# E-18_M_2.net
KiCad netlist of a schematic drawn in Altium Designer
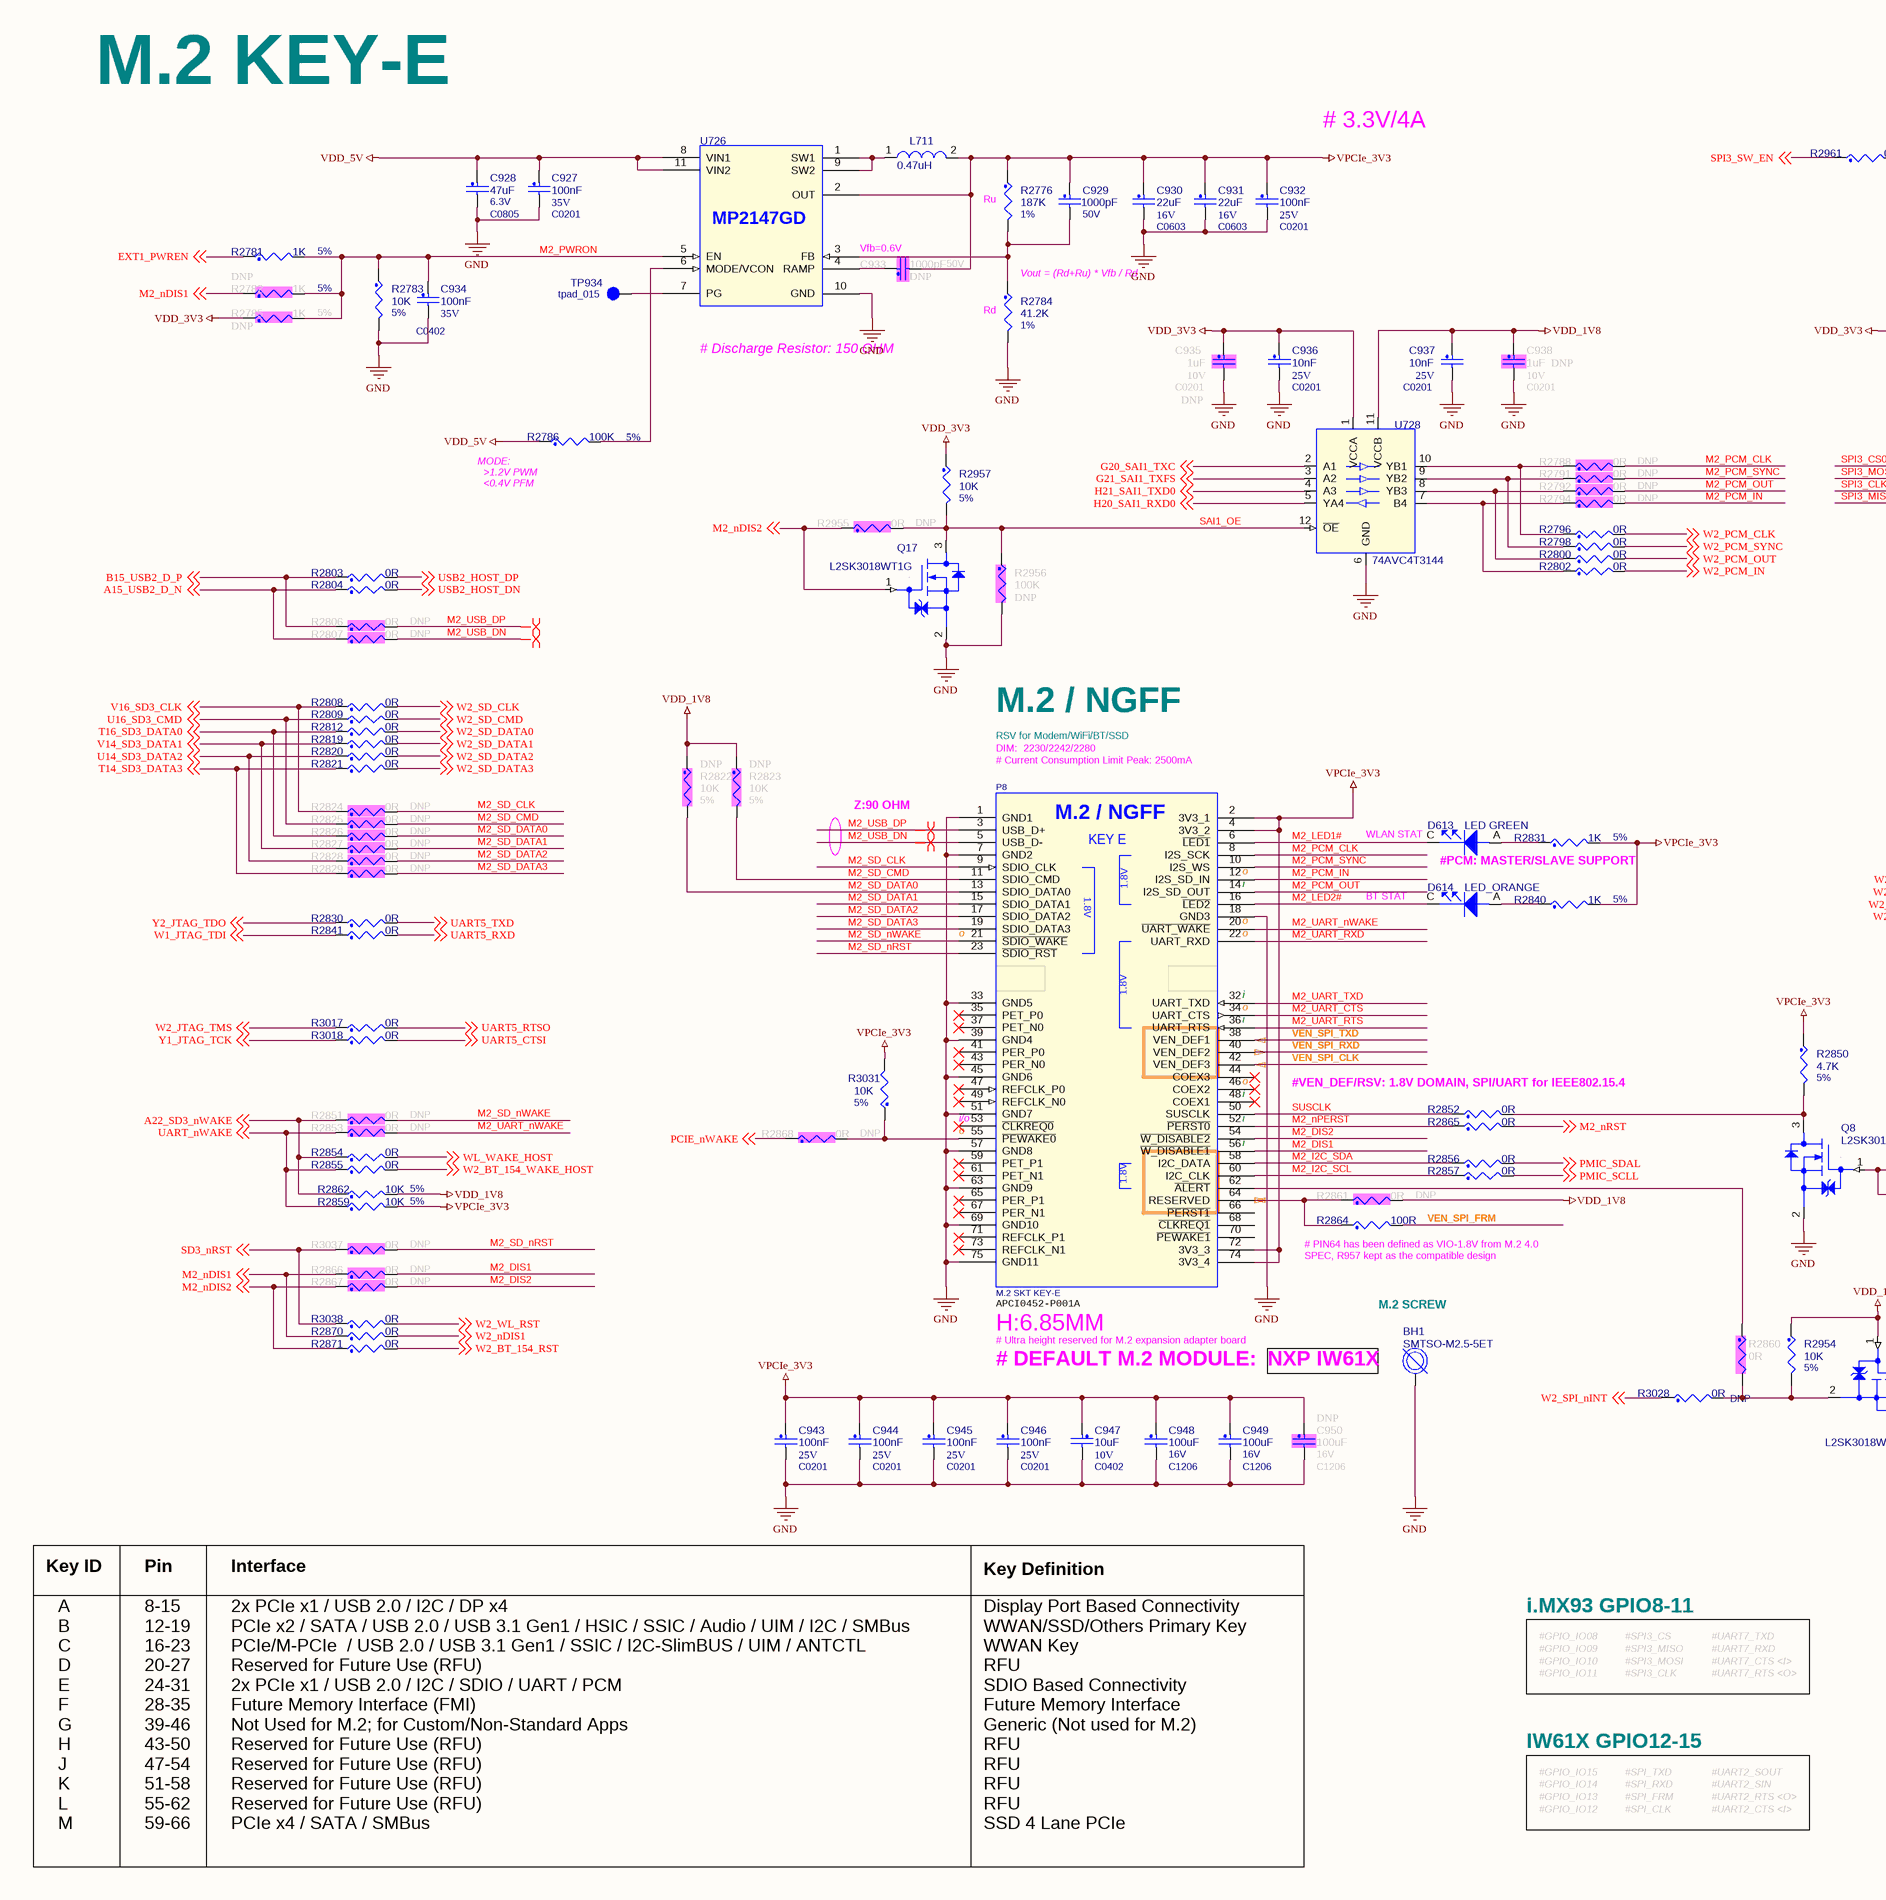
[diagram p0: E-18 M.2.SchDoc, left]
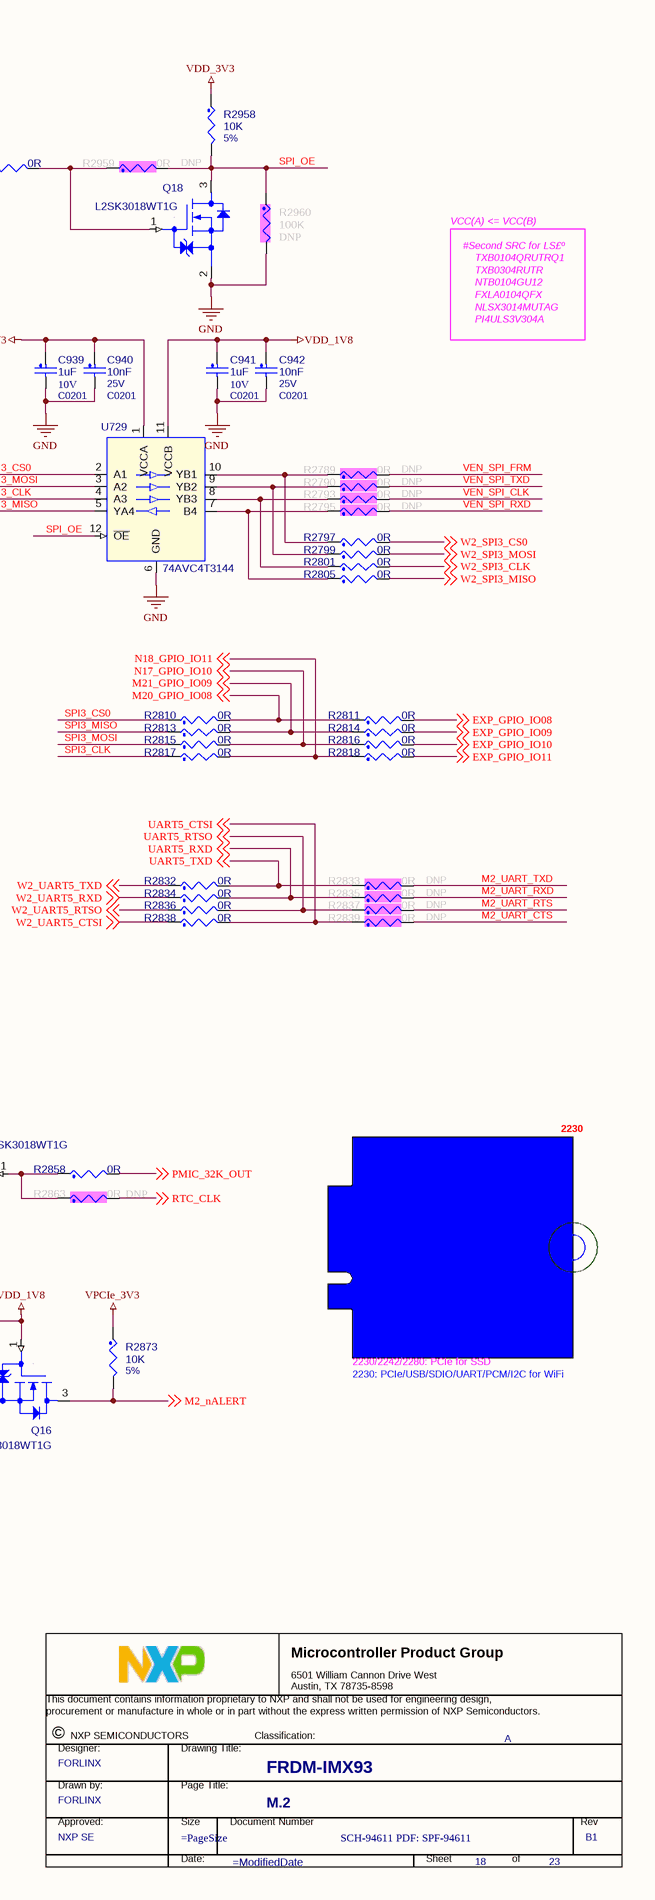
[diagram p1: E-18 M.2.SchDoc, right]

(export (version "E")
  (design (tool "Eeschema 10.0.6"))
  (components
    (comp (ref "BH1")
      (value "SMTSO-M2.5-5ET")
      (footprint "mh244-166t_202h")
      (description "M2mm,long 4mm")
      (libsource (lib "*") (part "MOUNT_HOLE"))
    )
    (comp (ref "C927")
      (value "100nF")
      (footprint "C0201")
      (description "0201,100nF,25V,+/-10%,X5R")
      (fields
        (field (name "VOLTAGE") "35V")
        (field (name "TOLERANCE") "10%")
        (field (name "PCB FOOTPRINT") "C0201")
      )
      (libsource (lib "*") (part "CAP_NP"))
    )
    (comp (ref "C928")
      (value "47uF")
      (footprint "C0805")
      (description "0805,47uF,10V,+/-20%,X5R")
      (fields
        (field (name "VOLTAGE") "6.3V")
        (field (name "TOLERANCE") "20%")
        (field (name "PCB FOOTPRINT") "C0805")
      )
      (libsource (lib "*") (part "CAP_NP"))
    )
    (comp (ref "C929")
      (value "1000pF")
      (footprint "C0402")
      (description "0402,1nF,50V,+/-10%,X7R")
      (fields (field (name "TOLERANCE") "5%") (field (name "VOLTAGE") "50V"))
      (libsource (lib "*") (part "CAP_NP"))
    )
    (comp (ref "C930")
      (value "22uF")
      (footprint "C0603")
      (description "0603,22uF,6.3V,+/-20%,X5R")
      (fields
        (field (name "TOLERANCE") "20%")
        (field (name "VOLTAGE") "16V")
        (field (name "PCB FOOTPRINT") "C0603")
      )
      (libsource (lib "*") (part "CAP_NP"))
    )
    (comp (ref "C931")
      (value "22uF")
      (footprint "C0603")
      (description "0603,22uF,6.3V,+/-20%,X5R")
      (fields
        (field (name "TOLERANCE") "20%")
        (field (name "VOLTAGE") "16V")
        (field (name "PCB FOOTPRINT") "C0603")
      )
      (libsource (lib "*") (part "CAP_NP"))
    )
    (comp (ref "C932")
      (value "100nF")
      (footprint "C0201")
      (description "0201,100nF,25V,+/-10%,X5R")
      (fields
        (field (name "VOLTAGE") "25V")
        (field (name "TOLERANCE") "10%")
        (field (name "PCB FOOTPRINT") "C0201")
      )
      (libsource (lib "*") (part "CAP_NP"))
    )
    (comp (ref "C933")
      (value "1000pF")
      (footprint "C0402")
      (description "0402,1nF,50V,+/-10%,X7R")
      (fields (field (name "ASSY_OPT") "DNP") (field (name "VOLTAGE") "50V") (field (name "TOLERANCE") "5%"))
      (libsource (lib "*") (part "CAP_NP"))
    )
    (comp (ref "C934")
      (value "100nF")
      (footprint "C0402")
      (description "0402,100nF,50V,+/-10%,X5R")
      (fields
        (field (name "TOLERANCE") "10%")
        (field (name "VOLTAGE") "35V")
        (field (name "PCB FOOTPRINT") "C0402")
      )
      (libsource (lib "*") (part "CAP_NP"))
    )
    (comp (ref "C935")
      (value "1uF")
      (footprint "C0201")
      (description "0201,1uF,10V,+/-20%,X5R")
      (fields
        (field (name "ASSY_OPT") "DNP")
        (field (name "TOLERANCE") "10%")
        (field (name "VOLTAGE") "10V")
        (field (name "PCB FOOTPRINT") "C0201")
      )
      (libsource (lib "*") (part "CAP_NP"))
    )
    (comp (ref "C936")
      (value "10nF")
      (footprint "C0201")
      (description "0201,10nF,25V,+/-10%,X7R")
      (fields
        (field (name "TOLERANCE") "10%")
        (field (name "VOLTAGE") "25V")
        (field (name "PCB FOOTPRINT") "C0201")
      )
      (libsource (lib "*") (part "CAP_NP"))
    )
    (comp (ref "C937")
      (value "10nF")
      (footprint "C0201")
      (description "0201,10nF,25V,+/-10%,X7R")
      (fields
        (field (name "TOLERANCE") "10%")
        (field (name "VOLTAGE") "25V")
        (field (name "PCB FOOTPRINT") "C0201")
      )
      (libsource (lib "*") (part "CAP_NP"))
    )
    (comp (ref "C938")
      (value "1uF")
      (footprint "C0201")
      (description "0201,1uF,10V,+/-20%,X5R")
      (fields
        (field (name "ASSY_OPT") "DNP")
        (field (name "TOLERANCE") "10%")
        (field (name "VOLTAGE") "10V")
        (field (name "PCB FOOTPRINT") "C0201")
      )
      (libsource (lib "*") (part "CAP_NP"))
    )
    (comp (ref "C939")
      (value "1uF")
      (footprint "C0201")
      (description "0201,1uF,10V,+/-20%,X5R")
      (fields
        (field (name "TOLERANCE") "10%")
        (field (name "VOLTAGE") "10V")
        (field (name "PCB FOOTPRINT") "C0201")
      )
      (libsource (lib "*") (part "CAP_NP"))
    )
    (comp (ref "C940")
      (value "10nF")
      (footprint "C0201")
      (description "0201,10nF,25V,+/-10%,X7R")
      (fields
        (field (name "VOLTAGE") "25V")
        (field (name "TOLERANCE") "10%")
        (field (name "PCB FOOTPRINT") "C0201")
      )
      (libsource (lib "*") (part "CAP_NP"))
    )
    (comp (ref "C941")
      (value "1uF")
      (footprint "C0201")
      (description "0201,1uF,10V,+/-20%,X5R")
      (fields
        (field (name "TOLERANCE") "10%")
        (field (name "VOLTAGE") "10V")
        (field (name "PCB FOOTPRINT") "C0201")
      )
      (libsource (lib "*") (part "CAP_NP"))
    )
    (comp (ref "C942")
      (value "10nF")
      (footprint "C0201")
      (description "0201,10nF,25V,+/-10%,X7R")
      (fields
        (field (name "VOLTAGE") "25V")
        (field (name "TOLERANCE") "10%")
        (field (name "PCB FOOTPRINT") "C0201")
      )
      (libsource (lib "*") (part "CAP_NP"))
    )
    (comp (ref "C943")
      (value "100nF")
      (footprint "C0201")
      (description "0201,100nF,25V,+/-10%,X5R")
      (fields
        (field (name "VOLTAGE") "25V")
        (field (name "TOLERANCE") "10%")
        (field (name "PCB FOOTPRINT") "C0201")
      )
      (libsource (lib "*") (part "CAP_NP"))
    )
    (comp (ref "C944")
      (value "100nF")
      (footprint "C0201")
      (description "0201,100nF,25V,+/-10%,X5R")
      (fields
        (field (name "VOLTAGE") "25V")
        (field (name "TOLERANCE") "10%")
        (field (name "PCB FOOTPRINT") "C0201")
      )
      (libsource (lib "*") (part "CAP_NP"))
    )
    (comp (ref "C945")
      (value "100nF")
      (footprint "C0201")
      (description "0201,100nF,25V,+/-10%,X5R")
      (fields
        (field (name "TOLERANCE") "10%")
        (field (name "VOLTAGE") "25V")
        (field (name "PCB FOOTPRINT") "C0201")
      )
      (libsource (lib "*") (part "CAP_NP"))
    )
    (comp (ref "C946")
      (value "100nF")
      (footprint "C0201")
      (description "0201,100nF,25V,+/-10%,X5R")
      (fields
        (field (name "TOLERANCE") "10%")
        (field (name "VOLTAGE") "25V")
        (field (name "PCB FOOTPRINT") "C0201")
      )
      (libsource (lib "*") (part "CAP_NP"))
    )
    (comp (ref "C947")
      (value "10uF")
      (footprint "C0402")
      (description "0402,10uF,6.3V,+/-20%,X5R")
      (fields
        (field (name "VOLTAGE") "10V")
        (field (name "TOLERANCE") "20%")
        (field (name "PCB FOOTPRINT") "C0402")
      )
      (libsource (lib "*") (part "CAP_NP"))
    )
    (comp (ref "C948")
      (value "100uF")
      (footprint "C1206")
      (description "1206,100uF,6.3V,+/-20%,X5R")
      (fields
        (field (name "TOLERANCE") "20%")
        (field (name "VOLTAGE") "16V")
        (field (name "PCB FOOTPRINT") "C1206")
      )
      (libsource (lib "*") (part "CAP_NP"))
    )
    (comp (ref "C949")
      (value "100uF")
      (footprint "C1206")
      (description "1206,100uF,6.3V,+/-20%,X5R")
      (fields
        (field (name "TOLERANCE") "20%")
        (field (name "VOLTAGE") "16V")
        (field (name "PCB FOOTPRINT") "C1206")
      )
      (libsource (lib "*") (part "CAP_NP"))
    )
    (comp (ref "C950")
      (value "100uF")
      (footprint "C1206")
      (description "1206,100uF,6.3V,+/-20%,X5R")
      (fields
        (field (name "ASSY_OPT") "DNP")
        (field (name "TOLERANCE") "20%")
        (field (name "VOLTAGE") "16V")
        (field (name "PCB FOOTPRINT") "C1206")
      )
      (libsource (lib "*") (part "CAP_NP"))
    )
    (comp (ref "D613")
      (value "LED GREEN")
      (footprint "led0603")
      (description "LED GRN SGL 25MA SMT 0603")
      (fields (field (name "VOLTAGE") "2V"))
      (libsource (lib "*") (part "LED"))
    )
    (comp (ref "D614")
      (value "LED_ORANGE")
      (footprint "led0603")
      (description "LED BLUE SGL 20MA SMT 0603")
      (fields (field (name "VOLTAGE") "2v"))
      (libsource (lib "*") (part "LED"))
    )
    (comp (ref "L711")
      (value "0.47uH")
      (footprint "ind_sph2520")
      (description "0.47uh, 2.5*2.0*1.0mm ,4.4A")
      (fields (field (name "TOLERANCE") "20%"))
      (libsource (lib "*") (part "INDUCTOR"))
    )
    (comp (ref "P8")
      (value "M.2 SKT KEY-E")
      (footprint "con_75_0p5_22x9_ra1")
      (description "AP-APC1037-1,M.2,0.5PITCH,5.5mm,Support height of 3.9mm,KEY-E")
      (libsource (lib "*") (part "CON_67_FEMALE_RA_B"))
    )
    (comp (ref "Q8")
      (value "L2SK3018WT1G")
      (footprint "sc70_3")
      (libsource (lib "*") (part "NX3008NBKW_SOT323"))
    )
    (comp (ref "Q16")
      (value "L2SK3018WT1G")
      (footprint "sc70_3")
      (libsource (lib "*") (part "NX3008NBKW_SOT323"))
    )
    (comp (ref "Q17")
      (value "L2SK3018WT1G")
      (footprint "sc70_3")
      (libsource (lib "*") (part "NX3008NBKW_SOT323"))
    )
    (comp (ref "Q18")
      (value "L2SK3018WT1G")
      (footprint "sc70_3")
      (libsource (lib "*") (part "NX3008NBKW_SOT323"))
    )
    (comp (ref "R2776")
      (value "187K")
      (footprint "R0402")
      (description "0402,187K,+/-1%")
      (fields (field (name "TOLERANCE") "1%"))
      (libsource (lib "*") (part "RES"))
    )
    (comp (ref "R2781")
      (value "1K")
      (footprint "R0201")
      (description "0201,1K,+/-1%")
      (fields (field (name "TOLERANCE") "5%"))
      (libsource (lib "*") (part "RES"))
    )
    (comp (ref "R2782")
      (value "1K")
      (footprint "R0201")
      (description "0201,1K,+/-1%")
      (fields (field (name "ASSY_OPT") "DNP") (field (name "TOLERANCE") "5%"))
      (libsource (lib "*") (part "RES"))
    )
    (comp (ref "R2783")
      (value "10K")
      (footprint "R0201")
      (description "0201,10K,+/-5%")
      (fields (field (name "TOLERANCE") "5%"))
      (libsource (lib "*") (part "RES"))
    )
    (comp (ref "R2784")
      (value "41.2K")
      (footprint "R0402")
      (description "0402,41.2K,+/-1%")
      (fields (field (name "TOLERANCE") "1%"))
      (libsource (lib "*") (part "RES"))
    )
    (comp (ref "R2785")
      (value "1K")
      (footprint "R0201")
      (description "0201,1K,+/-1%")
      (fields (field (name "ASSY_OPT") "DNP") (field (name "TOLERANCE") "5%"))
      (libsource (lib "*") (part "RES"))
    )
    (comp (ref "R2786")
      (value "100K")
      (footprint "R0201")
      (description "0201,100K,+/-1%")
      (fields (field (name "TOLERANCE") "5%") (field (name "VOLTAGE") "50V"))
      (libsource (lib "*") (part "RES"))
    )
    (comp (ref "R2788")
      (value "0R")
      (footprint "R0402")
      (description "0402,0Ohm,+/-1%")
      (fields
        (field (name "ASSY_OPT") "DNP")
        (field (name "TOLERANCE") "5%")
        (field (name "VOLTAGE") "1/16W")
      )
      (libsource (lib "*") (part "RES"))
    )
    (comp (ref "R2789")
      (value "0R")
      (footprint "R0402")
      (description "0402,0Ohm,+/-1%")
      (fields
        (field (name "ASSY_OPT") "DNP")
        (field (name "TOLERANCE") "5%")
        (field (name "VOLTAGE") "1/16W")
      )
      (libsource (lib "*") (part "RES"))
    )
    (comp (ref "R2790")
      (value "0R")
      (footprint "R0402")
      (description "0402,0Ohm,+/-1%")
      (fields
        (field (name "ASSY_OPT") "DNP")
        (field (name "VOLTAGE") "1/16W")
        (field (name "TOLERANCE") "5%")
      )
      (libsource (lib "*") (part "RES"))
    )
    (comp (ref "R2791")
      (value "0R")
      (footprint "R0402")
      (description "0402,0Ohm,+/-1%")
      (fields
        (field (name "ASSY_OPT") "DNP")
        (field (name "VOLTAGE") "1/16W")
        (field (name "TOLERANCE") "5%")
      )
      (libsource (lib "*") (part "RES"))
    )
    (comp (ref "R2792")
      (value "0R")
      (footprint "R0402")
      (description "0402,0Ohm,+/-1%")
      (fields
        (field (name "ASSY_OPT") "DNP")
        (field (name "VOLTAGE") "1/16W")
        (field (name "TOLERANCE") "5%")
      )
      (libsource (lib "*") (part "RES"))
    )
    (comp (ref "R2793")
      (value "0R")
      (footprint "R0402")
      (description "0402,0Ohm,+/-1%")
      (fields
        (field (name "ASSY_OPT") "DNP")
        (field (name "TOLERANCE") "5%")
        (field (name "VOLTAGE") "1/16W")
      )
      (libsource (lib "*") (part "RES"))
    )
    (comp (ref "R2794")
      (value "0R")
      (footprint "R0402")
      (description "0402,0Ohm,+/-1%")
      (fields
        (field (name "ASSY_OPT") "DNP")
        (field (name "VOLTAGE") "1/16W")
        (field (name "TOLERANCE") "5%")
      )
      (libsource (lib "*") (part "RES"))
    )
    (comp (ref "R2795")
      (value "0R")
      (footprint "R0402")
      (description "0402,0Ohm,+/-1%")
      (fields
        (field (name "ASSY_OPT") "DNP")
        (field (name "TOLERANCE") "5%")
        (field (name "VOLTAGE") "1/16W")
      )
      (libsource (lib "*") (part "RES"))
    )
    (comp (ref "R2796")
      (value "0R")
      (footprint "R0402")
      (description "0402,0Ohm,+/-1%")
      (fields (field (name "TOLERANCE") "5%") (field (name "VOLTAGE") "1/16W"))
      (libsource (lib "*") (part "RES"))
    )
    (comp (ref "R2797")
      (value "0R")
      (footprint "R0402")
      (description "0402,0Ohm,+/-1%")
      (fields (field (name "VOLTAGE") "1/16W") (field (name "TOLERANCE") "5%"))
      (libsource (lib "*") (part "RES"))
    )
    (comp (ref "R2798")
      (value "0R")
      (footprint "R0402")
      (description "0402,0Ohm,+/-1%")
      (fields (field (name "TOLERANCE") "5%") (field (name "VOLTAGE") "1/16W"))
      (libsource (lib "*") (part "RES"))
    )
    (comp (ref "R2799")
      (value "0R")
      (footprint "R0402")
      (description "0402,0Ohm,+/-1%")
      (fields (field (name "TOLERANCE") "5%") (field (name "VOLTAGE") "1/16W"))
      (libsource (lib "*") (part "RES"))
    )
    (comp (ref "R2800")
      (value "0R")
      (footprint "R0402")
      (description "0402,0Ohm,+/-1%")
      (fields (field (name "TOLERANCE") "5%") (field (name "VOLTAGE") "1/16W"))
      (libsource (lib "*") (part "RES"))
    )
    (comp (ref "R2801")
      (value "0R")
      (footprint "R0402")
      (description "0402,0Ohm,+/-1%")
      (fields (field (name "TOLERANCE") "5%") (field (name "VOLTAGE") "1/16W"))
      (libsource (lib "*") (part "RES"))
    )
    (comp (ref "R2802")
      (value "0R")
      (footprint "R0402")
      (description "0402,0Ohm,+/-1%")
      (fields (field (name "TOLERANCE") "5%") (field (name "VOLTAGE") "1/16W"))
      (libsource (lib "*") (part "RES"))
    )
    (comp (ref "R2803")
      (value "0R")
      (footprint "R0402")
      (description "0402,0Ohm,+/-1%")
      (fields (field (name "VOLTAGE") "1/16W") (field (name "TOLERANCE") "5%"))
      (libsource (lib "*") (part "RES"))
    )
    (comp (ref "R2804")
      (value "0R")
      (footprint "R0402")
      (description "0402,0Ohm,+/-1%")
      (fields (field (name "VOLTAGE") "1/16W") (field (name "TOLERANCE") "5%"))
      (libsource (lib "*") (part "RES"))
    )
    (comp (ref "R2805")
      (value "0R")
      (footprint "R0402")
      (description "0402,0Ohm,+/-1%")
      (fields (field (name "VOLTAGE") "1/16W") (field (name "TOLERANCE") "5%"))
      (libsource (lib "*") (part "RES"))
    )
    (comp (ref "R2806")
      (value "0R")
      (footprint "R0402")
      (description "0402,0Ohm,+/-1%")
      (fields
        (field (name "ASSY_OPT") "DNP")
        (field (name "VOLTAGE") "1/16W")
        (field (name "TOLERANCE") "5%")
      )
      (libsource (lib "*") (part "RES"))
    )
    (comp (ref "R2807")
      (value "0R")
      (footprint "R0402")
      (description "0402,0Ohm,+/-1%")
      (fields
        (field (name "ASSY_OPT") "DNP")
        (field (name "VOLTAGE") "1/16W")
        (field (name "TOLERANCE") "5%")
      )
      (libsource (lib "*") (part "RES"))
    )
    (comp (ref "R2808")
      (value "0R")
      (footprint "R0402")
      (description "0402,0Ohm,+/-1%")
      (fields (field (name "TOLERANCE") "5%") (field (name "VOLTAGE") "1/16W"))
      (libsource (lib "*") (part "RES"))
    )
    (comp (ref "R2809")
      (value "0R")
      (footprint "R0402")
      (description "0402,0Ohm,+/-1%")
      (fields (field (name "TOLERANCE") "5%") (field (name "VOLTAGE") "1/16W"))
      (libsource (lib "*") (part "RES"))
    )
    (comp (ref "R2810")
      (value "0R")
      (footprint "R0402")
      (description "0402,0Ohm,+/-1%")
      (fields (field (name "TOLERANCE") "5%") (field (name "VOLTAGE") "1/16W"))
      (libsource (lib "*") (part "RES"))
    )
    (comp (ref "R2811")
      (value "0R")
      (footprint "R0402")
      (description "0402,0Ohm,+/-1%")
      (fields (field (name "TOLERANCE") "5%") (field (name "VOLTAGE") "1/16W"))
      (libsource (lib "*") (part "RES"))
    )
    (comp (ref "R2812")
      (value "0R")
      (footprint "R0402")
      (description "0402,0Ohm,+/-1%")
      (fields (field (name "TOLERANCE") "5%") (field (name "VOLTAGE") "1/16W"))
      (libsource (lib "*") (part "RES"))
    )
    (comp (ref "R2813")
      (value "0R")
      (footprint "R0402")
      (description "0402,0Ohm,+/-1%")
      (fields (field (name "VOLTAGE") "1/16W") (field (name "TOLERANCE") "5%"))
      (libsource (lib "*") (part "RES"))
    )
    (comp (ref "R2814")
      (value "0R")
      (footprint "R0402")
      (description "0402,0Ohm,+/-1%")
      (fields (field (name "VOLTAGE") "1/16W") (field (name "TOLERANCE") "5%"))
      (libsource (lib "*") (part "RES"))
    )
    (comp (ref "R2815")
      (value "0R")
      (footprint "R0402")
      (description "0402,0Ohm,+/-1%")
      (fields (field (name "VOLTAGE") "1/16W") (field (name "TOLERANCE") "5%"))
      (libsource (lib "*") (part "RES"))
    )
    (comp (ref "R2816")
      (value "0R")
      (footprint "R0402")
      (description "0402,0Ohm,+/-1%")
      (fields (field (name "VOLTAGE") "1/16W") (field (name "TOLERANCE") "5%"))
      (libsource (lib "*") (part "RES"))
    )
    (comp (ref "R2817")
      (value "0R")
      (footprint "R0402")
      (description "0402,0Ohm,+/-1%")
      (fields (field (name "VOLTAGE") "1/16W") (field (name "TOLERANCE") "5%"))
      (libsource (lib "*") (part "RES"))
    )
    (comp (ref "R2818")
      (value "0R")
      (footprint "R0402")
      (description "0402,0Ohm,+/-1%")
      (fields (field (name "VOLTAGE") "1/16W") (field (name "TOLERANCE") "5%"))
      (libsource (lib "*") (part "RES"))
    )
    (comp (ref "R2819")
      (value "0R")
      (footprint "R0402")
      (description "0402,0Ohm,+/-1%")
      (fields (field (name "TOLERANCE") "5%") (field (name "VOLTAGE") "1/16W"))
      (libsource (lib "*") (part "RES"))
    )
    (comp (ref "R2820")
      (value "0R")
      (footprint "R0402")
      (description "0402,0Ohm,+/-1%")
      (fields (field (name "VOLTAGE") "1/16W") (field (name "TOLERANCE") "5%"))
      (libsource (lib "*") (part "RES"))
    )
    (comp (ref "R2821")
      (value "0R")
      (footprint "R0402")
      (description "0402,0Ohm,+/-1%")
      (fields (field (name "TOLERANCE") "5%") (field (name "VOLTAGE") "1/16W"))
      (libsource (lib "*") (part "RES"))
    )
    (comp (ref "R2822")
      (value "10K")
      (footprint "R0402")
      (description "0402,10K,+/-1%")
      (fields (field (name "ASSY_OPT") "DNP") (field (name "TOLERANCE") "5%"))
      (libsource (lib "*") (part "RES"))
    )
    (comp (ref "R2823")
      (value "10K")
      (footprint "R0402")
      (description "0402,10K,+/-1%")
      (fields (field (name "ASSY_OPT") "DNP") (field (name "TOLERANCE") "5%"))
      (libsource (lib "*") (part "RES"))
    )
    (comp (ref "R2824")
      (value "0R")
      (footprint "R0402")
      (description "0402,0Ohm,+/-1%")
      (fields
        (field (name "ASSY_OPT") "DNP")
        (field (name "VOLTAGE") "1/16W")
        (field (name "TOLERANCE") "5%")
      )
      (libsource (lib "*") (part "RES"))
    )
    (comp (ref "R2825")
      (value "0R")
      (footprint "R0402")
      (description "0402,0Ohm,+/-1%")
      (fields
        (field (name "ASSY_OPT") "DNP")
        (field (name "VOLTAGE") "1/16W")
        (field (name "TOLERANCE") "5%")
      )
      (libsource (lib "*") (part "RES"))
    )
    (comp (ref "R2826")
      (value "0R")
      (footprint "R0402")
      (description "0402,0Ohm,+/-1%")
      (fields
        (field (name "ASSY_OPT") "DNP")
        (field (name "VOLTAGE") "1/16W")
        (field (name "TOLERANCE") "5%")
      )
      (libsource (lib "*") (part "RES"))
    )
    (comp (ref "R2827")
      (value "0R")
      (footprint "R0402")
      (description "0402,0Ohm,+/-1%")
      (fields
        (field (name "ASSY_OPT") "DNP")
        (field (name "VOLTAGE") "1/16W")
        (field (name "TOLERANCE") "5%")
      )
      (libsource (lib "*") (part "RES"))
    )
    (comp (ref "R2828")
      (value "0R")
      (footprint "R0402")
      (description "0402,0Ohm,+/-1%")
      (fields
        (field (name "ASSY_OPT") "DNP")
        (field (name "VOLTAGE") "1/16W")
        (field (name "TOLERANCE") "5%")
      )
      (libsource (lib "*") (part "RES"))
    )
    (comp (ref "R2829")
      (value "0R")
      (footprint "R0402")
      (description "0402,0Ohm,+/-1%")
      (fields
        (field (name "ASSY_OPT") "DNP")
        (field (name "VOLTAGE") "1/16W")
        (field (name "TOLERANCE") "5%")
      )
      (libsource (lib "*") (part "RES"))
    )
    (comp (ref "R2830")
      (value "0R")
      (footprint "R0402")
      (description "0402,0Ohm,+/-1%")
      (fields (field (name "VOLTAGE") "1/16W") (field (name "TOLERANCE") "5%"))
      (libsource (lib "*") (part "RES"))
    )
    (comp (ref "R2831")
      (value "1K")
      (footprint "R0201")
      (description "0201,1K,+/-1%")
      (fields (field (name "TOLERANCE") "5%"))
      (libsource (lib "*") (part "RES"))
    )
    (comp (ref "R2832")
      (value "0R")
      (footprint "R0402")
      (description "0402,0Ohm,+/-1%")
      (fields (field (name "VOLTAGE") "1/16W") (field (name "TOLERANCE") "5%"))
      (libsource (lib "*") (part "RES"))
    )
    (comp (ref "R2833")
      (value "0R")
      (footprint "R0402")
      (description "0402,0Ohm,+/-1%")
      (fields
        (field (name "ASSY_OPT") "DNP")
        (field (name "VOLTAGE") "1/16W")
        (field (name "TOLERANCE") "5%")
      )
      (libsource (lib "*") (part "RES"))
    )
    (comp (ref "R2834")
      (value "0R")
      (footprint "R0402")
      (description "0402,0Ohm,+/-1%")
      (fields (field (name "TOLERANCE") "5%") (field (name "VOLTAGE") "1/16W"))
      (libsource (lib "*") (part "RES"))
    )
    (comp (ref "R2835")
      (value "0R")
      (footprint "R0402")
      (description "0402,0Ohm,+/-1%")
      (fields
        (field (name "ASSY_OPT") "DNP")
        (field (name "VOLTAGE") "1/16W")
        (field (name "TOLERANCE") "5%")
      )
      (libsource (lib "*") (part "RES"))
    )
    (comp (ref "R2836")
      (value "0R")
      (footprint "R0402")
      (description "0402,0Ohm,+/-1%")
      (fields (field (name "TOLERANCE") "5%") (field (name "VOLTAGE") "1/16W"))
      (libsource (lib "*") (part "RES"))
    )
    (comp (ref "R2837")
      (value "0R")
      (footprint "R0402")
      (description "0402,0Ohm,+/-1%")
      (fields
        (field (name "ASSY_OPT") "DNP")
        (field (name "VOLTAGE") "1/16W")
        (field (name "TOLERANCE") "5%")
      )
      (libsource (lib "*") (part "RES"))
    )
    (comp (ref "R2838")
      (value "0R")
      (footprint "R0402")
      (description "0402,0Ohm,+/-1%")
      (fields (field (name "VOLTAGE") "1/16W") (field (name "TOLERANCE") "5%"))
      (libsource (lib "*") (part "RES"))
    )
    (comp (ref "R2839")
      (value "0R")
      (footprint "R0402")
      (description "0402,0Ohm,+/-1%")
      (fields
        (field (name "ASSY_OPT") "DNP")
        (field (name "VOLTAGE") "1/16W")
        (field (name "TOLERANCE") "5%")
      )
      (libsource (lib "*") (part "RES"))
    )
    (comp (ref "R2840")
      (value "1K")
      (footprint "R0201")
      (description "0201,1K,+/-1%")
      (fields (field (name "TOLERANCE") "5%"))
      (libsource (lib "*") (part "RES"))
    )
    (comp (ref "R2841")
      (value "0R")
      (footprint "R0402")
      (description "0402,0Ohm,+/-1%")
      (fields (field (name "TOLERANCE") "5%") (field (name "VOLTAGE") "1/16W"))
      (libsource (lib "*") (part "RES"))
    )
    (comp (ref "R2850")
      (value "4.7K")
      (footprint "R0402")
      (description "0402,4.7K,+/-1%")
      (fields (field (name "TOLERANCE") "5%"))
      (libsource (lib "*") (part "RES"))
    )
    (comp (ref "R2851")
      (value "0R")
      (footprint "R0402")
      (description "0402,0Ohm,+/-1%")
      (fields
        (field (name "ASSY_OPT") "DNP")
        (field (name "VOLTAGE") "1/16W")
        (field (name "TOLERANCE") "5%")
      )
      (libsource (lib "*") (part "RES"))
    )
    (comp (ref "R2852")
      (value "0R")
      (footprint "R0201")
      (description "0201,0Ohm,+/-5%")
      (fields (field (name "VOLTAGE") "1/16W") (field (name "TOLERANCE") "5%"))
      (libsource (lib "*") (part "RES"))
    )
    (comp (ref "R2853")
      (value "0R")
      (footprint "R0402")
      (description "0402,0Ohm,+/-1%")
      (fields
        (field (name "ASSY_OPT") "DNP")
        (field (name "TOLERANCE") "5%")
        (field (name "VOLTAGE") "1/16W")
      )
      (libsource (lib "*") (part "RES"))
    )
    (comp (ref "R2854")
      (value "0R")
      (footprint "R0402")
      (description "0402,0Ohm,+/-1%")
      (fields (field (name "VOLTAGE") "1/16W") (field (name "TOLERANCE") "5%"))
      (libsource (lib "*") (part "RES"))
    )
    (comp (ref "R2855")
      (value "0R")
      (footprint "R0402")
      (description "0402,0Ohm,+/-1%")
      (fields (field (name "VOLTAGE") "1/16W") (field (name "TOLERANCE") "5%"))
      (libsource (lib "*") (part "RES"))
    )
    (comp (ref "R2856")
      (value "0R")
      (footprint "R0201")
      (description "0201,0Ohm,+/-5%")
      (fields (field (name "TOLERANCE") "5%") (field (name "VOLTAGE") "1/16W"))
      (libsource (lib "*") (part "RES"))
    )
    (comp (ref "R2857")
      (value "0R")
      (footprint "R0201")
      (description "0201,0Ohm,+/-5%")
      (fields (field (name "TOLERANCE") "5%") (field (name "VOLTAGE") "1/16W"))
      (libsource (lib "*") (part "RES"))
    )
    (comp (ref "R2858")
      (value "0R")
      (footprint "R0201")
      (description "0201,0Ohm,+/-5%")
      (fields (field (name "VOLTAGE") "1/16W") (field (name "TOLERANCE") "5%"))
      (libsource (lib "*") (part "RES"))
    )
    (comp (ref "R2859")
      (value "10K")
      (footprint "R0201")
      (description "0201,10K,+/-5%")
      (fields (field (name "TOLERANCE") "5%"))
      (libsource (lib "*") (part "RES"))
    )
    (comp (ref "R2860")
      (value "0R")
      (footprint "R0402")
      (description "0402,0Ohm,+/-1%")
      (fields
        (field (name "ASSY_OPT") "DNP")
        (field (name "TOLERANCE") "5%")
        (field (name "VOLTAGE") "1/16W")
      )
      (libsource (lib "*") (part "RES"))
    )
    (comp (ref "R2861")
      (value "0R")
      (footprint "R0201")
      (description "0201,0Ohm,+/-5%")
      (fields
        (field (name "ASSY_OPT") "DNP")
        (field (name "TOLERANCE") "5%")
        (field (name "VOLTAGE") "1/16W")
      )
      (libsource (lib "*") (part "RES"))
    )
    (comp (ref "R2862")
      (value "10K")
      (footprint "R0201")
      (description "0201,10K,+/-5%")
      (fields (field (name "TOLERANCE") "5%"))
      (libsource (lib "*") (part "RES"))
    )
    (comp (ref "R2863")
      (value "0R")
      (footprint "R0201")
      (description "0201,0Ohm,+/-5%")
      (fields
        (field (name "ASSY_OPT") "DNP")
        (field (name "TOLERANCE") "5%")
        (field (name "VOLTAGE") "1/16W")
      )
      (libsource (lib "*") (part "RES"))
    )
    (comp (ref "R2864")
      (value "100R")
      (footprint "R0201")
      (description "0201,100Ohm,+/-1%")
      (fields (field (name "TOLERANCE") "5%"))
      (libsource (lib "*") (part "RES"))
    )
    (comp (ref "R2865")
      (value "0R")
      (footprint "R0201")
      (description "0201,0Ohm,+/-5%")
      (fields (field (name "TOLERANCE") "5%") (field (name "VOLTAGE") "1/16W"))
      (libsource (lib "*") (part "RES"))
    )
    (comp (ref "R2866")
      (value "0R")
      (footprint "R0402")
      (description "0402,0Ohm,+/-1%")
      (fields
        (field (name "ASSY_OPT") "DNP")
        (field (name "TOLERANCE") "5%")
        (field (name "VOLTAGE") "1/16W")
      )
      (libsource (lib "*") (part "RES"))
    )
    (comp (ref "R2867")
      (value "0R")
      (footprint "R0402")
      (description "0402,0Ohm,+/-1%")
      (fields
        (field (name "ASSY_OPT") "DNP")
        (field (name "VOLTAGE") "1/16W")
        (field (name "TOLERANCE") "5%")
      )
      (libsource (lib "*") (part "RES"))
    )
    (comp (ref "R2868")
      (value "0R")
      (footprint "R0201")
      (description "0201,0Ohm,+/-5%")
      (fields
        (field (name "ASSY_OPT") "DNP")
        (field (name "TOLERANCE") "5%")
        (field (name "VOLTAGE") "1/16W")
      )
      (libsource (lib "*") (part "RES"))
    )
    (comp (ref "R2870")
      (value "0R")
      (footprint "R0402")
      (description "0402,0Ohm,+/-1%")
      (fields (field (name "VOLTAGE") "1/16W") (field (name "TOLERANCE") "5%"))
      (libsource (lib "*") (part "RES"))
    )
    (comp (ref "R2871")
      (value "0R")
      (footprint "R0402")
      (description "0402,0Ohm,+/-1%")
      (fields (field (name "VOLTAGE") "1/16W") (field (name "TOLERANCE") "5%"))
      (libsource (lib "*") (part "RES"))
    )
    (comp (ref "R2873")
      (value "10K")
      (footprint "R0201")
      (description "0201,10K,+/-5%")
      (fields (field (name "TOLERANCE") "5%"))
      (libsource (lib "*") (part "RES"))
    )
    (comp (ref "R2954")
      (value "10K")
      (footprint "R0201")
      (description "0201,10K,+/-5%")
      (fields (field (name "TOLERANCE") "5%"))
      (libsource (lib "*") (part "RES"))
    )
    (comp (ref "R2955")
      (value "0R")
      (footprint "R0201")
      (description "0201,0Ohm,+/-5%")
      (fields
        (field (name "ASSY_OPT") "DNP")
        (field (name "TOLERANCE") "5%")
        (field (name "VOLTAGE") "1/16W")
      )
      (libsource (lib "*") (part "RES"))
    )
    (comp (ref "R2956")
      (value "100K")
      (footprint "R0201")
      (description "0201,100K,+/-1%")
      (fields (field (name "ASSY_OPT") "DNP") (field (name "TOLERANCE") "5%"))
      (libsource (lib "*") (part "RES"))
    )
    (comp (ref "R2957")
      (value "10K")
      (footprint "R0201")
      (description "0201,10K,+/-5%")
      (fields (field (name "TOLERANCE") "5%"))
      (libsource (lib "*") (part "RES"))
    )
    (comp (ref "R2958")
      (value "10K")
      (footprint "R0201")
      (description "0201,10K,+/-5%")
      (fields (field (name "TOLERANCE") "5%"))
      (libsource (lib "*") (part "RES"))
    )
    (comp (ref "R2959")
      (value "0R")
      (footprint "R0201")
      (description "0201,0Ohm,+/-5%")
      (fields
        (field (name "ASSY_OPT") "DNP")
        (field (name "VOLTAGE") "1/16W")
        (field (name "TOLERANCE") "5%")
      )
      (libsource (lib "*") (part "RES"))
    )
    (comp (ref "R2960")
      (value "100K")
      (footprint "R0201")
      (description "0201,100K,+/-1%")
      (fields (field (name "ASSY_OPT") "DNP") (field (name "TOLERANCE") "5%"))
      (libsource (lib "*") (part "RES"))
    )
    (comp (ref "R2961")
      (value "0R")
      (footprint "R0201")
      (description "0201,0Ohm,+/-5%")
      (fields (field (name "TOLERANCE") "5%") (field (name "VOLTAGE") "1/16W"))
      (libsource (lib "*") (part "RES"))
    )
    (comp (ref "R3017")
      (value "0R")
      (footprint "R0402")
      (description "0402,0Ohm,+/-1%")
      (fields (field (name "VOLTAGE") "1/16W") (field (name "TOLERANCE") "5%"))
      (libsource (lib "*") (part "RES"))
    )
    (comp (ref "R3018")
      (value "0R")
      (footprint "R0402")
      (description "0402,0Ohm,+/-1%")
      (fields (field (name "TOLERANCE") "5%") (field (name "VOLTAGE") "1/16W"))
      (libsource (lib "*") (part "RES"))
    )
    (comp (ref "R3028")
      (value "0R")
      (footprint "R0402")
      (description "0402,0Ohm,+/-1%")
      (fields (field (name "TOLERANCE") "5%") (field (name "VOLTAGE") "1/16W"))
      (libsource (lib "*") (part "RES"))
    )
    (comp (ref "R3031")
      (value "10K")
      (footprint "R0201")
      (description "0201,10K,+/-5%")
      (fields (field (name "TOLERANCE") "5%"))
      (libsource (lib "*") (part "RES"))
    )
    (comp (ref "R3037")
      (value "0R")
      (footprint "R0402")
      (description "0402,0Ohm,+/-1%")
      (fields
        (field (name "ASSY_OPT") "DNP")
        (field (name "VOLTAGE") "1/16W")
        (field (name "TOLERANCE") "5%")
      )
      (libsource (lib "*") (part "RES"))
    )
    (comp (ref "R3038")
      (value "0R")
      (footprint "R0402")
      (description "0402,0Ohm,+/-1%")
      (fields (field (name "VOLTAGE") "1/16W") (field (name "TOLERANCE") "5%"))
      (libsource (lib "*") (part "RES"))
    )
    (comp (ref "TP934")
      (value "TPAD_015")
      (footprint "tpad_015")
      (description "no part to order")
      (fields (field (name "PCB FOOTPRINT") "tpad_015"))
      (libsource (lib "*") (part "TESTLOOP"))
    )
    (comp (ref "U726")
      (value "MP2147GD")
      (footprint "qfn12_0p5_2x3mm_ep")
      (libsource (lib "*") (part "MP2147GD_QFN_11P"))
    )
    (comp (ref "U728")
      (value "74AVC4T3144")
      (footprint "uqfn12_1p7x2mm")
      (description "74AVC4T3144GU12,XQFN12,1.70*2.0,4-bit dual-supply buffer/level translator;3-state")
      (fields (field (name "VOLTAGE") "0.9-3.6V"))
      (libsource (lib "*") (part "TXB0304RUT_12P_B_0"))
    )
    (comp (ref "U729")
      (value "74AVC4T3144")
      (footprint "uqfn12_1p7x2mm")
      (description "74AVC4T3144GU12,XQFN12,1.70*2.0,4-bit dual-supply buffer/level translator;3-state")
      (fields (field (name "VOLTAGE") "0.9-3.6V"))
      (libsource (lib "*") (part "TXB0304RUT_12P_B_0"))
    )
  )
  (nets
    (net (code "1") (name "/M2_DIS1") (class "Default")
      (node (ref "P8") (pin "56") (pinfunction "~{W_DISABLE1}_56") (pintype "passive"))
      (node (ref "R2866") (pin "2") (pinfunction "2_2") (pintype "passive"))
    )
    (net (code "2") (name "/M2_DIS2") (class "Default")
      (node (ref "P8") (pin "54") (pinfunction "~{W_DISABLE2}_54") (pintype "passive"))
      (node (ref "R2867") (pin "2") (pinfunction "2_2") (pintype "passive"))
    )
    (net (code "3") (name "/M2_I2C_SCL") (class "Default")
      (node (ref "P8") (pin "60") (pinfunction "I2C_CLK_60") (pintype "passive"))
      (node (ref "R2857") (pin "1") (pinfunction "1_1") (pintype "passive"))
    )
    (net (code "4") (name "/M2_I2C_SDA") (class "Default")
      (node (ref "P8") (pin "58") (pinfunction "I2C_DATA_58") (pintype "passive"))
      (node (ref "R2856") (pin "1") (pinfunction "1_1") (pintype "passive"))
    )
    (net (code "5") (name "/M2_LED1#") (class "Default")
      (node (ref "D613") (pin "C") (pinfunction "CATHODE_C") (pintype "passive"))
      (node (ref "P8") (pin "6") (pinfunction "~{LED1}_6") (pintype "passive"))
    )
    (net (code "6") (name "/M2_LED2#") (class "Default")
      (node (ref "D614") (pin "C") (pinfunction "CATHODE_C") (pintype "passive"))
      (node (ref "P8") (pin "16") (pinfunction "~{LED2}_16") (pintype "passive"))
    )
    (net (code "7") (name "/M2_PCM_CLK") (class "Default")
      (node (ref "P8") (pin "8") (pinfunction "I2S_SCK_8") (pintype "passive"))
      (node (ref "R2788") (pin "2") (pinfunction "2_2") (pintype "passive"))
    )
    (net (code "8") (name "/M2_PCM_IN") (class "Default")
      (node (ref "P8") (pin "12") (pinfunction "I2S_SD_IN_12") (pintype "passive"))
      (node (ref "R2794") (pin "2") (pinfunction "2_2") (pintype "passive"))
    )
    (net (code "9") (name "/M2_PCM_OUT") (class "Default")
      (node (ref "P8") (pin "14") (pinfunction "I2S_SD_OUT_14") (pintype "passive"))
      (node (ref "R2792") (pin "2") (pinfunction "2_2") (pintype "passive"))
    )
    (net (code "10") (name "/M2_PCM_SYNC") (class "Default")
      (node (ref "P8") (pin "10") (pinfunction "I2S_WS_10") (pintype "passive"))
      (node (ref "R2791") (pin "2") (pinfunction "2_2") (pintype "passive"))
    )
    (net (code "11") (name "/M2_PWRON") (class "Default")
      (node (ref "C934") (pin "1") (pinfunction "1_1") (pintype "passive"))
      (node (ref "R2781") (pin "2") (pinfunction "2_2") (pintype "passive"))
      (node (ref "R2782") (pin "2") (pinfunction "2_2") (pintype "passive"))
      (node (ref "R2783") (pin "1") (pinfunction "1_1") (pintype "passive"))
      (node (ref "R2785") (pin "2") (pinfunction "2_2") (pintype "passive"))
      (node (ref "U726") (pin "5") (pinfunction "EN_5") (pintype "input"))
    )
    (net (code "12") (name "/M2_SD_CLK") (class "Default")
      (node (ref "P8") (pin "9") (pinfunction "SDIO_CLK_9") (pintype "input"))
      (node (ref "R2824") (pin "2") (pinfunction "2_2") (pintype "passive"))
    )
    (net (code "13") (name "/M2_SD_CMD") (class "Default")
      (node (ref "P8") (pin "11") (pinfunction "SDIO_CMD_11") (pintype "passive"))
      (node (ref "R2823") (pin "2") (pinfunction "2_2") (pintype "passive"))
      (node (ref "R2825") (pin "2") (pinfunction "2_2") (pintype "passive"))
    )
    (net (code "14") (name "/M2_SD_DATA0") (class "Default")
      (node (ref "P8") (pin "13") (pinfunction "SDIO_DATA0_13") (pintype "passive"))
      (node (ref "R2822") (pin "2") (pinfunction "2_2") (pintype "passive"))
      (node (ref "R2826") (pin "2") (pinfunction "2_2") (pintype "passive"))
    )
    (net (code "15") (name "/M2_SD_DATA1") (class "Default")
      (node (ref "P8") (pin "15") (pinfunction "SDIO_DATA1_15") (pintype "passive"))
      (node (ref "R2827") (pin "2") (pinfunction "2_2") (pintype "passive"))
    )
    (net (code "16") (name "/M2_SD_DATA2") (class "Default")
      (node (ref "P8") (pin "17") (pinfunction "SDIO_DATA2_17") (pintype "passive"))
      (node (ref "R2828") (pin "2") (pinfunction "2_2") (pintype "passive"))
    )
    (net (code "17") (name "/M2_SD_DATA3") (class "Default")
      (node (ref "P8") (pin "19") (pinfunction "SDIO_DATA3_19") (pintype "passive"))
      (node (ref "R2829") (pin "2") (pinfunction "2_2") (pintype "passive"))
    )
    (net (code "18") (name "/M2_SD_nRST") (class "Default")
      (node (ref "P8") (pin "23") (pinfunction "~{SDIO_RST}_23") (pintype "passive"))
      (node (ref "R3037") (pin "2") (pinfunction "2_2") (pintype "passive"))
    )
    (net (code "19") (name "/M2_SD_nWAKE") (class "Default")
      (node (ref "P8") (pin "21") (pinfunction "~{SDIO_WAKE}_21") (pintype "passive"))
      (node (ref "R2851") (pin "2") (pinfunction "2_2") (pintype "passive"))
    )
    (net (code "20") (name "/M2_UART_CTS") (class "Default")
      (node (ref "P8") (pin "34") (pinfunction "UART_CTS_34") (pintype "output"))
      (node (ref "R2839") (pin "2") (pinfunction "2_2") (pintype "passive"))
    )
    (net (code "21") (name "/M2_UART_RTS") (class "Default")
      (node (ref "P8") (pin "36") (pinfunction "UART_RTS_36") (pintype "input"))
      (node (ref "R2837") (pin "2") (pinfunction "2_2") (pintype "passive"))
    )
    (net (code "22") (name "/M2_UART_RXD") (class "Default")
      (node (ref "P8") (pin "22") (pinfunction "UART_RXD_22") (pintype "passive"))
      (node (ref "R2835") (pin "2") (pinfunction "2_2") (pintype "passive"))
    )
    (net (code "23") (name "/M2_UART_TXD") (class "Default")
      (node (ref "P8") (pin "32") (pinfunction "UART_TXD_32") (pintype "input"))
      (node (ref "R2833") (pin "2") (pinfunction "2_2") (pintype "passive"))
    )
    (net (code "24") (name "/M2_UART_nWAKE") (class "Default")
      (node (ref "P8") (pin "20") (pinfunction "~{UART_WAKE}_20") (pintype "passive"))
      (node (ref "R2853") (pin "2") (pinfunction "2_2") (pintype "passive"))
    )
    (net (code "25") (name "/M2_USB_DN") (class "Default")
      (node (ref "P8") (pin "5") (pinfunction "USB_D-_5") (pintype "passive"))
      (node (ref "R2807") (pin "2") (pinfunction "2_2") (pintype "passive"))
    )
    (net (code "26") (name "/M2_USB_DP") (class "Default")
      (node (ref "P8") (pin "3") (pinfunction "USB_D+_3") (pintype "passive"))
      (node (ref "R2806") (pin "2") (pinfunction "2_2") (pintype "passive"))
    )
    (net (code "27") (name "/M2_nPERST") (class "Default")
      (node (ref "P8") (pin "52") (pinfunction "~{PERST0}_52") (pintype "passive"))
      (node (ref "R2865") (pin "1") (pinfunction "1_1") (pintype "passive"))
    )
    (net (code "28") (name "/SAI1_OE") (class "Default")
      (node (ref "Q17") (pin "3") (pinfunction "DRAIN_3") (pintype "passive"))
      (node (ref "R2955") (pin "2") (pinfunction "2_2") (pintype "passive"))
      (node (ref "R2956") (pin "1") (pinfunction "1_1") (pintype "passive"))
      (node (ref "R2957") (pin "2") (pinfunction "2_2") (pintype "passive"))
      (node (ref "U728") (pin "12") (pinfunction "~{OE}_12") (pintype "input"))
    )
    (net (code "29") (name "/SPI3_CLK") (class "Default")
      (node (ref "R2817") (pin "1") (pinfunction "1_1") (pintype "passive"))
      (node (ref "U729") (pin "4") (pinfunction "A3_4") (pintype "bidirectional"))
    )
    (net (code "30") (name "/SPI3_CS0") (class "Default")
      (node (ref "R2810") (pin "1") (pinfunction "1_1") (pintype "passive"))
      (node (ref "U729") (pin "2") (pinfunction "A1_2") (pintype "bidirectional"))
    )
    (net (code "31") (name "/SPI3_MISO") (class "Default")
      (node (ref "R2813") (pin "1") (pinfunction "1_1") (pintype "passive"))
      (node (ref "U729") (pin "5") (pinfunction "YA4_5") (pintype "bidirectional"))
    )
    (net (code "32") (name "/SPI3_MOSI") (class "Default")
      (node (ref "R2815") (pin "1") (pinfunction "1_1") (pintype "passive"))
      (node (ref "U729") (pin "3") (pinfunction "A2_3") (pintype "bidirectional"))
    )
    (net (code "33") (name "/SPI_OE") (class "Default")
      (node (ref "Q18") (pin "3") (pinfunction "DRAIN_3") (pintype "passive"))
      (node (ref "R2958") (pin "2") (pinfunction "2_2") (pintype "passive"))
      (node (ref "R2959") (pin "2") (pinfunction "2_2") (pintype "passive"))
      (node (ref "R2960") (pin "1") (pinfunction "1_1") (pintype "passive"))
      (node (ref "U729") (pin "12") (pinfunction "~{OE}_12") (pintype "input"))
    )
    (net (code "34") (name "/SUSCLK") (class "Default")
      (node (ref "P8") (pin "50") (pinfunction "SUSCLK_50") (pintype "passive"))
      (node (ref "R2852") (pin "1") (pinfunction "1_1") (pintype "passive"))
    )
    (net (code "35") (name "/VEN_SPI_CLK") (class "Default")
      (node (ref "P8") (pin "42") (pinfunction "VEN_DEF3_42") (pintype "passive"))
      (node (ref "R2793") (pin "2") (pinfunction "2_2") (pintype "passive"))
    )
    (net (code "36") (name "/VEN_SPI_FRM") (class "Default")
      (node (ref "R2789") (pin "2") (pinfunction "2_2") (pintype "passive"))
      (node (ref "R2864") (pin "2") (pinfunction "2_2") (pintype "passive"))
    )
    (net (code "37") (name "/VEN_SPI_RXD") (class "Default")
      (node (ref "P8") (pin "40") (pinfunction "VEN_DEF2_40") (pintype "passive"))
      (node (ref "R2795") (pin "2") (pinfunction "2_2") (pintype "passive"))
    )
    (net (code "38") (name "/VEN_SPI_TXD") (class "Default")
      (node (ref "P8") (pin "38") (pinfunction "VEN_DEF1_38") (pintype "passive"))
      (node (ref "R2790") (pin "2") (pinfunction "2_2") (pintype "passive"))
    )
    (net (code "39") (name "A15_USB2_D_N") (class "Default")
      (node (ref "R2804") (pin "1") (pinfunction "1_1") (pintype "passive"))
      (node (ref "R2807") (pin "1") (pinfunction "1_1") (pintype "passive"))
    )
    (net (code "40") (name "A22_SD3_nWAKE") (class "Default")
      (node (ref "R2851") (pin "1") (pinfunction "1_1") (pintype "passive"))
      (node (ref "R2854") (pin "1") (pinfunction "1_1") (pintype "passive"))
      (node (ref "R2862") (pin "1") (pinfunction "1_1") (pintype "passive"))
    )
    (net (code "41") (name "B15_USB2_D_P") (class "Default")
      (node (ref "R2803") (pin "1") (pinfunction "1_1") (pintype "passive"))
      (node (ref "R2806") (pin "1") (pinfunction "1_1") (pintype "passive"))
    )
    (net (code "42") (name "EXP_GPIO_IO08") (class "Default")
      (node (ref "R2811") (pin "2") (pinfunction "2_2") (pintype "passive"))
    )
    (net (code "43") (name "EXP_GPIO_IO09") (class "Default")
      (node (ref "R2814") (pin "2") (pinfunction "2_2") (pintype "passive"))
    )
    (net (code "44") (name "EXP_GPIO_IO10") (class "Default")
      (node (ref "R2816") (pin "2") (pinfunction "2_2") (pintype "passive"))
    )
    (net (code "45") (name "EXP_GPIO_IO11") (class "Default")
      (node (ref "R2818") (pin "2") (pinfunction "2_2") (pintype "passive"))
    )
    (net (code "46") (name "EXT1_PWREN") (class "Default")
      (node (ref "R2781") (pin "1") (pinfunction "1_1") (pintype "passive"))
    )
    (net (code "47") (name "G20_SAI1_TXC") (class "Default")
      (node (ref "U728") (pin "2") (pinfunction "A1_2") (pintype "bidirectional"))
    )
    (net (code "48") (name "G21_SAI1_TXFS") (class "Default")
      (node (ref "U728") (pin "3") (pinfunction "A2_3") (pintype "bidirectional"))
    )
    (net (code "49") (name "GND") (class "Default")
      (node (ref "BH1") (pin "1") (pinfunction "1_1") (pintype "passive"))
      (node (ref "C927") (pin "2") (pinfunction "2_2") (pintype "passive"))
      (node (ref "C928") (pin "2") (pinfunction "2_2") (pintype "passive"))
      (node (ref "C930") (pin "2") (pinfunction "2_2") (pintype "passive"))
      (node (ref "C931") (pin "2") (pinfunction "2_2") (pintype "passive"))
      (node (ref "C932") (pin "2") (pinfunction "2_2") (pintype "passive"))
      (node (ref "C934") (pin "2") (pinfunction "2_2") (pintype "passive"))
      (node (ref "C935") (pin "2") (pinfunction "2_2") (pintype "passive"))
      (node (ref "C936") (pin "2") (pinfunction "2_2") (pintype "passive"))
      (node (ref "C937") (pin "2") (pinfunction "2_2") (pintype "passive"))
      (node (ref "C938") (pin "2") (pinfunction "2_2") (pintype "passive"))
      (node (ref "C939") (pin "2") (pinfunction "2_2") (pintype "passive"))
      (node (ref "C940") (pin "2") (pinfunction "2_2") (pintype "passive"))
      (node (ref "C941") (pin "2") (pinfunction "2_2") (pintype "passive"))
      (node (ref "C942") (pin "2") (pinfunction "2_2") (pintype "passive"))
      (node (ref "C943") (pin "2") (pinfunction "2_2") (pintype "passive"))
      (node (ref "C944") (pin "2") (pinfunction "2_2") (pintype "passive"))
      (node (ref "C945") (pin "2") (pinfunction "2_2") (pintype "passive"))
      (node (ref "C946") (pin "2") (pinfunction "2_2") (pintype "passive"))
      (node (ref "C947") (pin "2") (pinfunction "2_2") (pintype "passive"))
      (node (ref "C948") (pin "2") (pinfunction "2_2") (pintype "passive"))
      (node (ref "C949") (pin "2") (pinfunction "2_2") (pintype "passive"))
      (node (ref "C950") (pin "2") (pinfunction "2_2") (pintype "passive"))
      (node (ref "P8") (pin "1") (pinfunction "GND1_1") (pintype "power_in"))
      (node (ref "P8") (pin "18") (pinfunction "GND3_18") (pintype "power_in"))
      (node (ref "P8") (pin "33") (pinfunction "GND5_33") (pintype "power_in"))
      (node (ref "P8") (pin "39") (pinfunction "GND4_39") (pintype "power_in"))
      (node (ref "P8") (pin "45") (pinfunction "GND6_45") (pintype "power_in"))
      (node (ref "P8") (pin "51") (pinfunction "GND7_51") (pintype "power_in"))
      (node (ref "P8") (pin "57") (pinfunction "GND8_57") (pintype "power_in"))
      (node (ref "P8") (pin "63") (pinfunction "GND9_63") (pintype "power_in"))
      (node (ref "P8") (pin "69") (pinfunction "GND10_69") (pintype "power_in"))
      (node (ref "P8") (pin "7") (pinfunction "GND2_7") (pintype "power_in"))
      (node (ref "P8") (pin "75") (pinfunction "GND11_75") (pintype "power_in"))
      (node (ref "Q17") (pin "2") (pinfunction "SOURCE_2") (pintype "passive"))
      (node (ref "Q18") (pin "2") (pinfunction "SOURCE_2") (pintype "passive"))
      (node (ref "Q8") (pin "2") (pinfunction "SOURCE_2") (pintype "passive"))
      (node (ref "R2783") (pin "2") (pinfunction "2_2") (pintype "passive"))
      (node (ref "R2784") (pin "2") (pinfunction "2_2") (pintype "passive"))
      (node (ref "R2956") (pin "2") (pinfunction "2_2") (pintype "passive"))
      (node (ref "R2960") (pin "2") (pinfunction "2_2") (pintype "passive"))
      (node (ref "U726") (pin "10") (pinfunction "GND_10") (pintype "power_in"))
      (node (ref "U728") (pin "6") (pinfunction "GND_6") (pintype "power_in"))
      (node (ref "U729") (pin "6") (pinfunction "GND_6") (pintype "power_in"))
    )
    (net (code "50") (name "H20_SAI1_RXD0") (class "Default")
      (node (ref "U728") (pin "5") (pinfunction "YA4_5") (pintype "bidirectional"))
    )
    (net (code "51") (name "H21_SAI1_TXD0") (class "Default")
      (node (ref "U728") (pin "4") (pinfunction "A3_4") (pintype "bidirectional"))
    )
    (net (code "52") (name "M2_nALERT") (class "Default")
      (node (ref "Q16") (pin "3") (pinfunction "DRAIN_3") (pintype "passive"))
      (node (ref "R2873") (pin "2") (pinfunction "2_2") (pintype "passive"))
    )
    (net (code "53") (name "M2_nDIS1") (class "Default")
      (node (ref "R2782") (pin "1") (pinfunction "1_1") (pintype "passive"))
      (node (ref "R2866") (pin "1") (pinfunction "1_1") (pintype "passive"))
      (node (ref "R2870") (pin "1") (pinfunction "1_1") (pintype "passive"))
    )
    (net (code "54") (name "M2_nDIS2") (class "Default")
      (node (ref "Q17") (pin "1") (pinfunction "GATE_1") (pintype "input"))
      (node (ref "R2867") (pin "1") (pinfunction "1_1") (pintype "passive"))
      (node (ref "R2871") (pin "1") (pinfunction "1_1") (pintype "passive"))
      (node (ref "R2955") (pin "1") (pinfunction "1_1") (pintype "passive"))
    )
    (net (code "55") (name "M2_nRST") (class "Default")
      (node (ref "R2865") (pin "2") (pinfunction "2_2") (pintype "passive"))
    )
    (net (code "56") (name "M20_GPIO_IO08") (class "Default")
      (node (ref "R2810") (pin "2") (pinfunction "2_2") (pintype "passive"))
      (node (ref "R2811") (pin "1") (pinfunction "1_1") (pintype "passive"))
    )
    (net (code "57") (name "M21_GPIO_IO09") (class "Default")
      (node (ref "R2813") (pin "2") (pinfunction "2_2") (pintype "passive"))
      (node (ref "R2814") (pin "1") (pinfunction "1_1") (pintype "passive"))
    )
    (net (code "58") (name "N17_GPIO_IO10") (class "Default")
      (node (ref "R2815") (pin "2") (pinfunction "2_2") (pintype "passive"))
      (node (ref "R2816") (pin "1") (pinfunction "1_1") (pintype "passive"))
    )
    (net (code "59") (name "N18_GPIO_IO11") (class "Default")
      (node (ref "R2817") (pin "2") (pinfunction "2_2") (pintype "passive"))
      (node (ref "R2818") (pin "1") (pinfunction "1_1") (pintype "passive"))
    )
    (net (code "60") (name "Net-(D613-ANODE)") (class "Default")
      (node (ref "D613") (pin "A") (pinfunction "ANODE_A") (pintype "passive"))
      (node (ref "R2831") (pin "1") (pinfunction "1_1") (pintype "passive"))
    )
    (net (code "61") (name "Net-(D614-ANODE)") (class "Default")
      (node (ref "D614") (pin "A") (pinfunction "ANODE_A") (pintype "passive"))
      (node (ref "R2840") (pin "1") (pinfunction "1_1") (pintype "passive"))
    )
    (net (code "62") (name "Net-(P8-RESERVED)") (class "Default")
      (node (ref "P8") (pin "64") (pinfunction "RESERVED_64") (pintype "passive"))
      (node (ref "R2861") (pin "1") (pinfunction "1_1") (pintype "passive"))
      (node (ref "R2864") (pin "1") (pinfunction "1_1") (pintype "passive"))
    )
    (net (code "63") (name "Net-(P8-~{ALERT})") (class "Default")
      (node (ref "P8") (pin "62") (pinfunction "~{ALERT}_62") (pintype "passive"))
      (node (ref "R2860") (pin "1") (pinfunction "1_1") (pintype "passive"))
    )
    (net (code "64") (name "Net-(P8-~{PEWAKE0})") (class "Default")
      (node (ref "P8") (pin "55") (pinfunction "~{PEWAKE0}_55") (pintype "passive"))
      (node (ref "R2868") (pin "2") (pinfunction "2_2") (pintype "passive"))
      (node (ref "R3031") (pin "1") (pinfunction "1_1") (pintype "passive"))
    )
    (net (code "65") (name "Net-(Q8-DRAIN)") (class "Default")
      (node (ref "Q8") (pin "3") (pinfunction "DRAIN_3") (pintype "passive"))
      (node (ref "R2850") (pin "2") (pinfunction "2_2") (pintype "passive"))
      (node (ref "R2852") (pin "2") (pinfunction "2_2") (pintype "passive"))
    )
    (net (code "66") (name "Net-(Q8-GATE)") (class "Default")
      (node (ref "Q8") (pin "1") (pinfunction "GATE_1") (pintype "input"))
      (node (ref "R2858") (pin "1") (pinfunction "1_1") (pintype "passive"))
      (node (ref "R2863") (pin "1") (pinfunction "1_1") (pintype "passive"))
    )
    (net (code "67") (name "Net-(Q16-SOURCE)") (class "Default")
      (node (ref "Q16") (pin "2") (pinfunction "SOURCE_2") (pintype "passive"))
      (node (ref "R2860") (pin "2") (pinfunction "2_2") (pintype "passive"))
      (node (ref "R2954") (pin "2") (pinfunction "2_2") (pintype "passive"))
      (node (ref "R3028") (pin "2") (pinfunction "2_2") (pintype "passive"))
    )
    (net (code "68") (name "Net-(Q18-GATE)") (class "Default")
      (node (ref "Q18") (pin "1") (pinfunction "GATE_1") (pintype "input"))
      (node (ref "R2959") (pin "1") (pinfunction "1_1") (pintype "passive"))
      (node (ref "R2961") (pin "2") (pinfunction "2_2") (pintype "passive"))
    )
    (net (code "69") (name "Net-(TP934-Pin1)") (class "Default")
      (node (ref "TP934") (pin "1") (pinfunction "Pin1_1") (pintype "passive"))
      (node (ref "U726") (pin "7") (pinfunction "PG_7") (pintype "open_collector"))
    )
    (net (code "70") (name "Net-(U726-FB)") (class "Default")
      (node (ref "C929") (pin "2") (pinfunction "2_2") (pintype "passive"))
      (node (ref "R2776") (pin "2") (pinfunction "2_2") (pintype "passive"))
      (node (ref "R2784") (pin "1") (pinfunction "1_1") (pintype "passive"))
      (node (ref "U726") (pin "3") (pinfunction "FB_3") (pintype "input"))
    )
    (net (code "71") (name "Net-(U726-MODE{slash}VCON)") (class "Default")
      (node (ref "R2786") (pin "2") (pinfunction "2_2") (pintype "passive"))
      (node (ref "U726") (pin "6") (pinfunction "MODE/VCON_6") (pintype "input"))
    )
    (net (code "72") (name "Net-(U726-RAMP)") (class "Default")
      (node (ref "C933") (pin "1") (pinfunction "1_1") (pintype "passive"))
      (node (ref "U726") (pin "4") (pinfunction "RAMP_4") (pintype "passive"))
    )
    (net (code "73") (name "Net-(U726-SW1)") (class "Default")
      (node (ref "L711") (pin "1") (pinfunction "1_1") (pintype "passive"))
      (node (ref "U726") (pin "1") (pinfunction "SW1_1") (pintype "power_in"))
      (node (ref "U726") (pin "9") (pinfunction "SW2_9") (pintype "power_in"))
    )
    (net (code "74") (name "Net-(U728-B4)") (class "Default")
      (node (ref "R2794") (pin "1") (pinfunction "1_1") (pintype "passive"))
      (node (ref "R2802") (pin "1") (pinfunction "1_1") (pintype "passive"))
      (node (ref "U728") (pin "7") (pinfunction "B4_7") (pintype "bidirectional"))
    )
    (net (code "75") (name "Net-(U728-YB1)") (class "Default")
      (node (ref "R2788") (pin "1") (pinfunction "1_1") (pintype "passive"))
      (node (ref "R2796") (pin "1") (pinfunction "1_1") (pintype "passive"))
      (node (ref "U728") (pin "10") (pinfunction "YB1_10") (pintype "bidirectional"))
    )
    (net (code "76") (name "Net-(U728-YB2)") (class "Default")
      (node (ref "R2791") (pin "1") (pinfunction "1_1") (pintype "passive"))
      (node (ref "R2798") (pin "1") (pinfunction "1_1") (pintype "passive"))
      (node (ref "U728") (pin "9") (pinfunction "YB2_9") (pintype "bidirectional"))
    )
    (net (code "77") (name "Net-(U728-YB3)") (class "Default")
      (node (ref "R2792") (pin "1") (pinfunction "1_1") (pintype "passive"))
      (node (ref "R2800") (pin "1") (pinfunction "1_1") (pintype "passive"))
      (node (ref "U728") (pin "8") (pinfunction "YB3_8") (pintype "bidirectional"))
    )
    (net (code "78") (name "Net-(U729-B4)") (class "Default")
      (node (ref "R2795") (pin "1") (pinfunction "1_1") (pintype "passive"))
      (node (ref "R2805") (pin "1") (pinfunction "1_1") (pintype "passive"))
      (node (ref "U729") (pin "7") (pinfunction "B4_7") (pintype "bidirectional"))
    )
    (net (code "79") (name "Net-(U729-YB1)") (class "Default")
      (node (ref "R2789") (pin "1") (pinfunction "1_1") (pintype "passive"))
      (node (ref "R2797") (pin "1") (pinfunction "1_1") (pintype "passive"))
      (node (ref "U729") (pin "10") (pinfunction "YB1_10") (pintype "bidirectional"))
    )
    (net (code "80") (name "Net-(U729-YB2)") (class "Default")
      (node (ref "R2790") (pin "1") (pinfunction "1_1") (pintype "passive"))
      (node (ref "R2799") (pin "1") (pinfunction "1_1") (pintype "passive"))
      (node (ref "U729") (pin "9") (pinfunction "YB2_9") (pintype "bidirectional"))
    )
    (net (code "81") (name "Net-(U729-YB3)") (class "Default")
      (node (ref "R2793") (pin "1") (pinfunction "1_1") (pintype "passive"))
      (node (ref "R2801") (pin "1") (pinfunction "1_1") (pintype "passive"))
      (node (ref "U729") (pin "8") (pinfunction "YB3_8") (pintype "bidirectional"))
    )
    (net (code "82") (name "PCIE_nWAKE") (class "Default")
      (node (ref "R2868") (pin "1") (pinfunction "1_1") (pintype "passive"))
    )
    (net (code "83") (name "PMIC_32K_OUT") (class "Default")
      (node (ref "R2858") (pin "2") (pinfunction "2_2") (pintype "passive"))
    )
    (net (code "84") (name "PMIC_SCLL") (class "Default")
      (node (ref "R2857") (pin "2") (pinfunction "2_2") (pintype "passive"))
    )
    (net (code "85") (name "PMIC_SDAL") (class "Default")
      (node (ref "R2856") (pin "2") (pinfunction "2_2") (pintype "passive"))
    )
    (net (code "86") (name "RTC_CLK") (class "Default")
      (node (ref "R2863") (pin "2") (pinfunction "2_2") (pintype "passive"))
    )
    (net (code "87") (name "SD3_nRST") (class "Default")
      (node (ref "R3037") (pin "1") (pinfunction "1_1") (pintype "passive"))
      (node (ref "R3038") (pin "1") (pinfunction "1_1") (pintype "passive"))
    )
    (net (code "88") (name "SPI3_SW_EN") (class "Default")
      (node (ref "R2961") (pin "1") (pinfunction "1_1") (pintype "passive"))
    )
    (net (code "89") (name "T14_SD3_DATA3") (class "Default")
      (node (ref "R2821") (pin "1") (pinfunction "1_1") (pintype "passive"))
      (node (ref "R2829") (pin "1") (pinfunction "1_1") (pintype "passive"))
    )
    (net (code "90") (name "T16_SD3_DATA0") (class "Default")
      (node (ref "R2812") (pin "1") (pinfunction "1_1") (pintype "passive"))
      (node (ref "R2826") (pin "1") (pinfunction "1_1") (pintype "passive"))
    )
    (net (code "91") (name "U14_SD3_DATA2") (class "Default")
      (node (ref "R2820") (pin "1") (pinfunction "1_1") (pintype "passive"))
      (node (ref "R2828") (pin "1") (pinfunction "1_1") (pintype "passive"))
    )
    (net (code "92") (name "U16_SD3_CMD") (class "Default")
      (node (ref "R2809") (pin "1") (pinfunction "1_1") (pintype "passive"))
      (node (ref "R2825") (pin "1") (pinfunction "1_1") (pintype "passive"))
    )
    (net (code "93") (name "UART5_CTSI") (class "Default")
      (node (ref "R2838") (pin "2") (pinfunction "2_2") (pintype "passive"))
      (node (ref "R2839") (pin "1") (pinfunction "1_1") (pintype "passive"))
      (node (ref "R3018") (pin "2") (pinfunction "2_2") (pintype "passive"))
    )
    (net (code "94") (name "UART5_RTSO") (class "Default")
      (node (ref "R2836") (pin "2") (pinfunction "2_2") (pintype "passive"))
      (node (ref "R2837") (pin "1") (pinfunction "1_1") (pintype "passive"))
      (node (ref "R3017") (pin "2") (pinfunction "2_2") (pintype "passive"))
    )
    (net (code "95") (name "UART5_RXD") (class "Default")
      (node (ref "R2834") (pin "2") (pinfunction "2_2") (pintype "passive"))
      (node (ref "R2835") (pin "1") (pinfunction "1_1") (pintype "passive"))
      (node (ref "R2841") (pin "2") (pinfunction "2_2") (pintype "passive"))
    )
    (net (code "96") (name "UART5_TXD") (class "Default")
      (node (ref "R2830") (pin "2") (pinfunction "2_2") (pintype "passive"))
      (node (ref "R2832") (pin "2") (pinfunction "2_2") (pintype "passive"))
      (node (ref "R2833") (pin "1") (pinfunction "1_1") (pintype "passive"))
    )
    (net (code "97") (name "UART_nWAKE") (class "Default")
      (node (ref "R2853") (pin "1") (pinfunction "1_1") (pintype "passive"))
      (node (ref "R2855") (pin "1") (pinfunction "1_1") (pintype "passive"))
      (node (ref "R2859") (pin "1") (pinfunction "1_1") (pintype "passive"))
    )
    (net (code "98") (name "USB2_HOST_DN") (class "Default")
      (node (ref "R2804") (pin "2") (pinfunction "2_2") (pintype "passive"))
    )
    (net (code "99") (name "USB2_HOST_DP") (class "Default")
      (node (ref "R2803") (pin "2") (pinfunction "2_2") (pintype "passive"))
    )
    (net (code "100") (name "V14_SD3_DATA1") (class "Default")
      (node (ref "R2819") (pin "1") (pinfunction "1_1") (pintype "passive"))
      (node (ref "R2827") (pin "1") (pinfunction "1_1") (pintype "passive"))
    )
    (net (code "101") (name "V16_SD3_CLK") (class "Default")
      (node (ref "R2808") (pin "1") (pinfunction "1_1") (pintype "passive"))
      (node (ref "R2824") (pin "1") (pinfunction "1_1") (pintype "passive"))
    )
    (net (code "102") (name "VDD_1V8") (class "Default")
      (node (ref "C937") (pin "1") (pinfunction "1_1") (pintype "passive"))
      (node (ref "C938") (pin "1") (pinfunction "1_1") (pintype "passive"))
      (node (ref "C941") (pin "1") (pinfunction "1_1") (pintype "passive"))
      (node (ref "C942") (pin "1") (pinfunction "1_1") (pintype "passive"))
      (node (ref "Q16") (pin "1") (pinfunction "GATE_1") (pintype "input"))
      (node (ref "R2822") (pin "1") (pinfunction "1_1") (pintype "passive"))
      (node (ref "R2823") (pin "1") (pinfunction "1_1") (pintype "passive"))
      (node (ref "R2861") (pin "2") (pinfunction "2_2") (pintype "passive"))
      (node (ref "R2862") (pin "2") (pinfunction "2_2") (pintype "passive"))
      (node (ref "R2954") (pin "1") (pinfunction "1_1") (pintype "passive"))
      (node (ref "U728") (pin "11") (pinfunction "VCCB_11") (pintype "power_in"))
      (node (ref "U729") (pin "11") (pinfunction "VCCB_11") (pintype "power_in"))
    )
    (net (code "103") (name "VDD_3V3") (class "Default")
      (node (ref "C935") (pin "1") (pinfunction "1_1") (pintype "passive"))
      (node (ref "C936") (pin "1") (pinfunction "1_1") (pintype "passive"))
      (node (ref "C939") (pin "1") (pinfunction "1_1") (pintype "passive"))
      (node (ref "C940") (pin "1") (pinfunction "1_1") (pintype "passive"))
      (node (ref "R2785") (pin "1") (pinfunction "1_1") (pintype "passive"))
      (node (ref "R2957") (pin "1") (pinfunction "1_1") (pintype "passive"))
      (node (ref "R2958") (pin "1") (pinfunction "1_1") (pintype "passive"))
      (node (ref "U728") (pin "1") (pinfunction "VCCA_1") (pintype "power_in"))
      (node (ref "U729") (pin "1") (pinfunction "VCCA_1") (pintype "power_in"))
    )
    (net (code "104") (name "VDD_5V") (class "Default")
      (node (ref "C927") (pin "1") (pinfunction "1_1") (pintype "passive"))
      (node (ref "C928") (pin "1") (pinfunction "1_1") (pintype "passive"))
      (node (ref "R2786") (pin "1") (pinfunction "1_1") (pintype "passive"))
      (node (ref "U726") (pin "11") (pinfunction "VIN2_11") (pintype "power_in"))
      (node (ref "U726") (pin "8") (pinfunction "VIN1_8") (pintype "power_in"))
    )
    (net (code "105") (name "VPCIe_3V3") (class "Default")
      (node (ref "C929") (pin "1") (pinfunction "1_1") (pintype "passive"))
      (node (ref "C930") (pin "1") (pinfunction "1_1") (pintype "passive"))
      (node (ref "C931") (pin "1") (pinfunction "1_1") (pintype "passive"))
      (node (ref "C932") (pin "1") (pinfunction "1_1") (pintype "passive"))
      (node (ref "C933") (pin "2") (pinfunction "2_2") (pintype "passive"))
      (node (ref "C943") (pin "1") (pinfunction "1_1") (pintype "passive"))
      (node (ref "C944") (pin "1") (pinfunction "1_1") (pintype "passive"))
      (node (ref "C945") (pin "1") (pinfunction "1_1") (pintype "passive"))
      (node (ref "C946") (pin "1") (pinfunction "1_1") (pintype "passive"))
      (node (ref "C947") (pin "1") (pinfunction "1_1") (pintype "passive"))
      (node (ref "C948") (pin "1") (pinfunction "1_1") (pintype "passive"))
      (node (ref "C949") (pin "1") (pinfunction "1_1") (pintype "passive"))
      (node (ref "C950") (pin "1") (pinfunction "1_1") (pintype "passive"))
      (node (ref "L711") (pin "2") (pinfunction "2_2") (pintype "passive"))
      (node (ref "P8") (pin "2") (pinfunction "3V3_1_2") (pintype "power_in"))
      (node (ref "P8") (pin "4") (pinfunction "3V3_2_4") (pintype "power_in"))
      (node (ref "P8") (pin "72") (pinfunction "3V3_3_72") (pintype "power_in"))
      (node (ref "P8") (pin "74") (pinfunction "3V3_4_74") (pintype "power_in"))
      (node (ref "R2776") (pin "1") (pinfunction "1_1") (pintype "passive"))
      (node (ref "R2831") (pin "2") (pinfunction "2_2") (pintype "passive"))
      (node (ref "R2840") (pin "2") (pinfunction "2_2") (pintype "passive"))
      (node (ref "R2850") (pin "1") (pinfunction "1_1") (pintype "passive"))
      (node (ref "R2859") (pin "2") (pinfunction "2_2") (pintype "passive"))
      (node (ref "R2873") (pin "1") (pinfunction "1_1") (pintype "passive"))
      (node (ref "R3031") (pin "2") (pinfunction "2_2") (pintype "passive"))
      (node (ref "U726") (pin "2") (pinfunction "OUT_2") (pintype "power_in"))
    )
    (net (code "106") (name "W1_JTAG_TDI") (class "Default")
      (node (ref "R2841") (pin "1") (pinfunction "1_1") (pintype "passive"))
    )
    (net (code "107") (name "W2_BT_154_RST") (class "Default")
      (node (ref "R2871") (pin "2") (pinfunction "2_2") (pintype "passive"))
    )
    (net (code "108") (name "W2_BT_154_WAKE_HOST") (class "Default")
      (node (ref "R2855") (pin "2") (pinfunction "2_2") (pintype "passive"))
    )
    (net (code "109") (name "W2_JTAG_TMS") (class "Default")
      (node (ref "R3017") (pin "1") (pinfunction "1_1") (pintype "passive"))
    )
    (net (code "110") (name "W2_PCM_CLK") (class "Default")
      (node (ref "R2796") (pin "2") (pinfunction "2_2") (pintype "passive"))
    )
    (net (code "111") (name "W2_PCM_IN") (class "Default")
      (node (ref "R2802") (pin "2") (pinfunction "2_2") (pintype "passive"))
    )
    (net (code "112") (name "W2_PCM_OUT") (class "Default")
      (node (ref "R2800") (pin "2") (pinfunction "2_2") (pintype "passive"))
    )
    (net (code "113") (name "W2_PCM_SYNC") (class "Default")
      (node (ref "R2798") (pin "2") (pinfunction "2_2") (pintype "passive"))
    )
    (net (code "114") (name "W2_SD_CLK") (class "Default")
      (node (ref "R2808") (pin "2") (pinfunction "2_2") (pintype "passive"))
    )
    (net (code "115") (name "W2_SD_CMD") (class "Default")
      (node (ref "R2809") (pin "2") (pinfunction "2_2") (pintype "passive"))
    )
    (net (code "116") (name "W2_SD_DATA0") (class "Default")
      (node (ref "R2812") (pin "2") (pinfunction "2_2") (pintype "passive"))
    )
    (net (code "117") (name "W2_SD_DATA1") (class "Default")
      (node (ref "R2819") (pin "2") (pinfunction "2_2") (pintype "passive"))
    )
    (net (code "118") (name "W2_SD_DATA2") (class "Default")
      (node (ref "R2820") (pin "2") (pinfunction "2_2") (pintype "passive"))
    )
    (net (code "119") (name "W2_SD_DATA3") (class "Default")
      (node (ref "R2821") (pin "2") (pinfunction "2_2") (pintype "passive"))
    )
    (net (code "120") (name "W2_SPI3_CLK") (class "Default")
      (node (ref "R2801") (pin "2") (pinfunction "2_2") (pintype "passive"))
    )
    (net (code "121") (name "W2_SPI3_CS0") (class "Default")
      (node (ref "R2797") (pin "2") (pinfunction "2_2") (pintype "passive"))
    )
    (net (code "122") (name "W2_SPI3_MISO") (class "Default")
      (node (ref "R2805") (pin "2") (pinfunction "2_2") (pintype "passive"))
    )
    (net (code "123") (name "W2_SPI3_MOSI") (class "Default")
      (node (ref "R2799") (pin "2") (pinfunction "2_2") (pintype "passive"))
    )
    (net (code "124") (name "W2_SPI_nINT") (class "Default")
      (node (ref "R3028") (pin "1") (pinfunction "1_1") (pintype "passive"))
    )
    (net (code "125") (name "W2_UART5_CTSI") (class "Default")
      (node (ref "R2838") (pin "1") (pinfunction "1_1") (pintype "passive"))
    )
    (net (code "126") (name "W2_UART5_RTSO") (class "Default")
      (node (ref "R2836") (pin "1") (pinfunction "1_1") (pintype "passive"))
    )
    (net (code "127") (name "W2_UART5_RXD") (class "Default")
      (node (ref "R2834") (pin "1") (pinfunction "1_1") (pintype "passive"))
    )
    (net (code "128") (name "W2_UART5_TXD") (class "Default")
      (node (ref "R2832") (pin "1") (pinfunction "1_1") (pintype "passive"))
    )
    (net (code "129") (name "W2_WL_RST") (class "Default")
      (node (ref "R3038") (pin "2") (pinfunction "2_2") (pintype "passive"))
    )
    (net (code "130") (name "W2_nDIS1") (class "Default")
      (node (ref "R2870") (pin "2") (pinfunction "2_2") (pintype "passive"))
    )
    (net (code "131") (name "WL_WAKE_HOST") (class "Default")
      (node (ref "R2854") (pin "2") (pinfunction "2_2") (pintype "passive"))
    )
    (net (code "132") (name "Y1_JTAG_TCK") (class "Default")
      (node (ref "R3018") (pin "1") (pinfunction "1_1") (pintype "passive"))
    )
    (net (code "133") (name "Y2_JTAG_TDO") (class "Default")
      (node (ref "R2830") (pin "1") (pinfunction "1_1") (pintype "passive"))
    )
    (net (code "134") (name "unconnected-(P8-COEX1-Pad48)") (class "Default")
      (node (ref "P8") (pin "48") (pinfunction "COEX1_48") (pintype "passive+no_connect"))
    )
    (net (code "135") (name "unconnected-(P8-COEX2-Pad46)") (class "Default")
      (node (ref "P8") (pin "46") (pinfunction "COEX2_46") (pintype "passive+no_connect"))
    )
    (net (code "136") (name "unconnected-(P8-COEX3-Pad44)") (class "Default")
      (node (ref "P8") (pin "44") (pinfunction "COEX3_44") (pintype "passive+no_connect"))
    )
    (net (code "137") (name "unconnected-(P8-PER_N0-Pad43)") (class "Default")
      (node (ref "P8") (pin "43") (pinfunction "PER_N0_43") (pintype "passive+no_connect"))
    )
    (net (code "138") (name "unconnected-(P8-PER_N1-Pad67)") (class "Default")
      (node (ref "P8") (pin "67") (pinfunction "PER_N1_67") (pintype "passive+no_connect"))
    )
    (net (code "139") (name "unconnected-(P8-PER_P0-Pad41)") (class "Default")
      (node (ref "P8") (pin "41") (pinfunction "PER_P0_41") (pintype "passive+no_connect"))
    )
    (net (code "140") (name "unconnected-(P8-PER_P1-Pad65)") (class "Default")
      (node (ref "P8") (pin "65") (pinfunction "PER_P1_65") (pintype "passive+no_connect"))
    )
    (net (code "141") (name "unconnected-(P8-PET_N0-Pad37)") (class "Default")
      (node (ref "P8") (pin "37") (pinfunction "PET_N0_37") (pintype "passive+no_connect"))
    )
    (net (code "142") (name "unconnected-(P8-PET_N1-Pad61)") (class "Default")
      (node (ref "P8") (pin "61") (pinfunction "PET_N1_61") (pintype "passive+no_connect"))
    )
    (net (code "143") (name "unconnected-(P8-PET_P0-Pad35)") (class "Default")
      (node (ref "P8") (pin "35") (pinfunction "PET_P0_35") (pintype "passive+no_connect"))
    )
    (net (code "144") (name "unconnected-(P8-PET_P1-Pad59)") (class "Default")
      (node (ref "P8") (pin "59") (pinfunction "PET_P1_59") (pintype "passive+no_connect"))
    )
    (net (code "145") (name "unconnected-(P8-REFCLK_N0-Pad49)") (class "Default")
      (node (ref "P8") (pin "49") (pinfunction "REFCLK_N0_49") (pintype "input+no_connect"))
    )
    (net (code "146") (name "unconnected-(P8-REFCLK_N1-Pad73)") (class "Default")
      (node (ref "P8") (pin "73") (pinfunction "REFCLK_N1_73") (pintype "passive+no_connect"))
    )
    (net (code "147") (name "unconnected-(P8-REFCLK_P0-Pad47)") (class "Default")
      (node (ref "P8") (pin "47") (pinfunction "REFCLK_P0_47") (pintype "input+no_connect"))
    )
    (net (code "148") (name "unconnected-(P8-REFCLK_P1-Pad71)") (class "Default")
      (node (ref "P8") (pin "71") (pinfunction "REFCLK_P1_71") (pintype "passive+no_connect"))
    )
    (net (code "149") (name "unconnected-(P8-~{CLKREQ0}-Pad53)") (class "Default")
      (node (ref "P8") (pin "53") (pinfunction "~{CLKREQ0}_53") (pintype "passive+no_connect"))
    )
    (net (code "150") (name "unconnected-(P8-~{CLKREQ1}-Pad68)") (class "Default")
      (node (ref "P8") (pin "68") (pinfunction "~{CLKREQ1}_68") (pintype "passive"))
    )
    (net (code "151") (name "unconnected-(P8-~{PERST1}-Pad66)") (class "Default")
      (node (ref "P8") (pin "66") (pinfunction "~{PERST1}_66") (pintype "passive"))
    )
    (net (code "152") (name "unconnected-(P8-~{PEWAKE1}-Pad70)") (class "Default")
      (node (ref "P8") (pin "70") (pinfunction "~{PEWAKE1}_70") (pintype "passive"))
    )
  )
)
